# sensors.net
KiCad netlist of a schematic drawn in Altium Designer
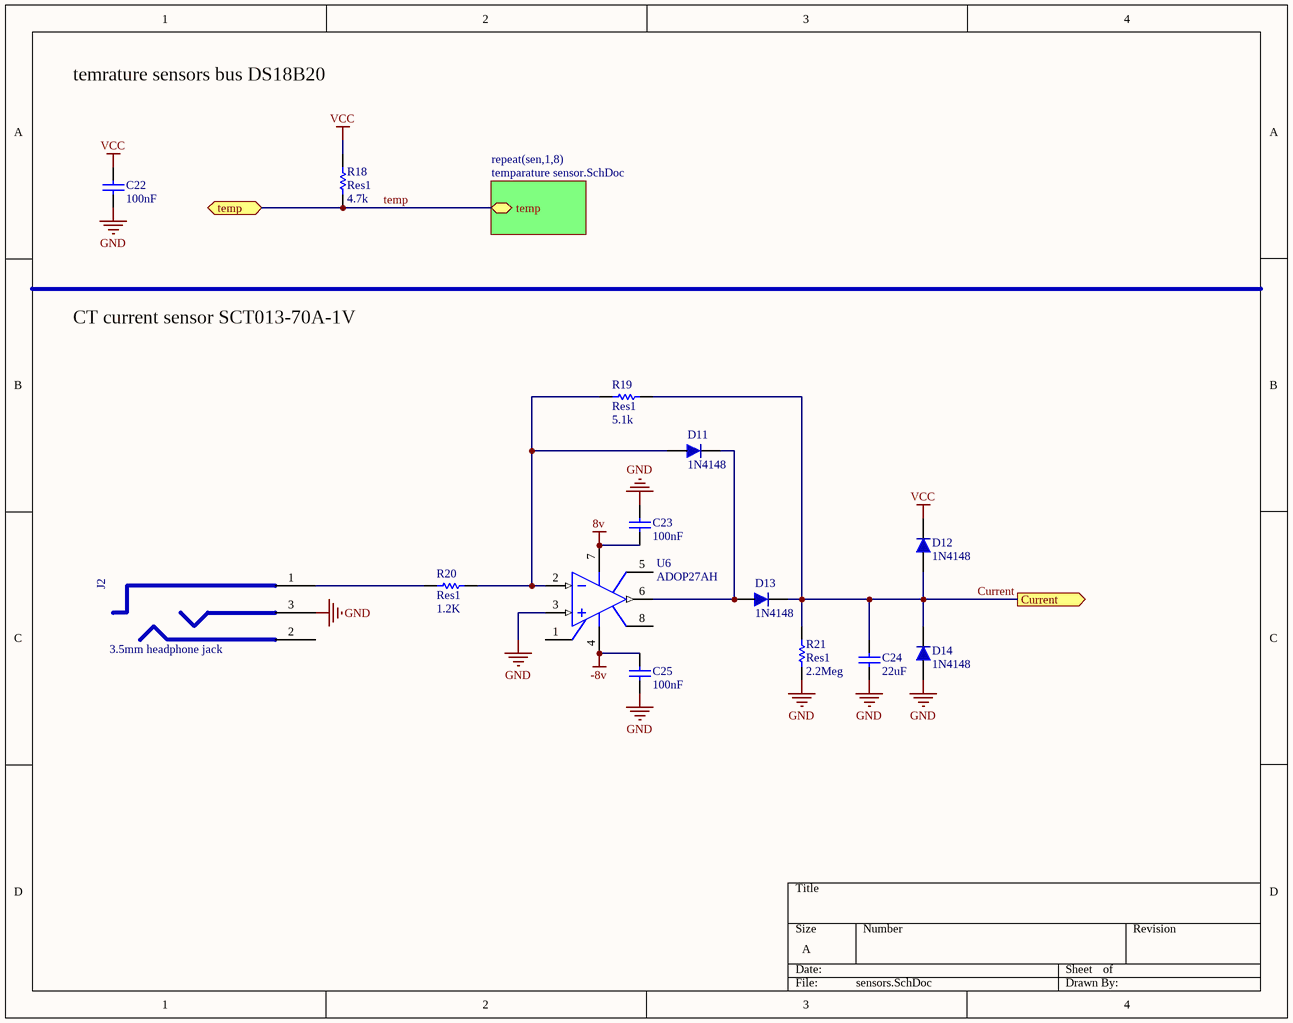
[diagram p0: sensors.SchDoc]

(export (version "E")
  (design (tool "Eeschema 10.0.6"))
  (components
    (comp (ref "C22")
      (value "100nF")
      (footprint "CAP 1206 (3216X15L)")
      (description "CAP-100Nf")
      (fields (field (name "Comment") "Cap"))
      (libsource (lib "Altium library (www.AVRelec.com)") (part "Cap ceramic"))
    )
    (comp (ref "C23")
      (value "100nF")
      (footprint "CAP 1206 (3216X15L)")
      (description "CAP-100Nf")
      (fields (field (name "Comment") "Cap"))
      (libsource (lib "Altium library (www.AVRelec.com)") (part "Cap ceramic"))
    )
    (comp (ref "C24")
      (value "22uF")
      (footprint "CAP 1206 (3216X15L)")
      (description "CAP-100Nf")
      (fields (field (name "Comment") "Cap"))
      (libsource (lib "Altium library (www.AVRelec.com)") (part "Cap ceramic"))
    )
    (comp (ref "C25")
      (value "100nF")
      (footprint "CAP 1206 (3216X15L)")
      (description "CAP-100Nf")
      (fields (field (name "Comment") "Cap"))
      (libsource (lib "Altium library (www.AVRelec.com)") (part "Cap ceramic"))
    )
    (comp (ref "D11")
      (value "1N4148")
      (footprint "LL4148")
      (description "DIODE GEN PURP 100V 200MA DO35")
      (fields (field (name "PUBLISHER") "Abbas Basereh"))
      (libsource (lib "Altium (2)") (part "1N4148"))
    )
    (comp (ref "D12")
      (value "1N4148")
      (footprint "LL4148")
      (description "DIODE GEN PURP 100V 200MA DO35")
      (fields (field (name "PUBLISHER") "Abbas Basereh"))
      (libsource (lib "Altium (2)") (part "1N4148"))
    )
    (comp (ref "D13")
      (value "1N4148")
      (footprint "LL4148")
      (description "DIODE GEN PURP 100V 200MA DO35")
      (fields (field (name "PUBLISHER") "Abbas Basereh"))
      (libsource (lib "Altium (2)") (part "1N4148"))
    )
    (comp (ref "D14")
      (value "1N4148")
      (footprint "LL4148")
      (description "DIODE GEN PURP 100V 200MA DO35")
      (fields (field (name "PUBLISHER") "Abbas Basereh"))
      (libsource (lib "Altium (2)") (part "1N4148"))
    )
    (comp (ref "J2")
      (value "3.5mm headphone jack")
      (footprint "phone jack")
      (libsource (lib "chiller") (part "phone jack"))
    )
    (comp (ref "R18")
      (value "Res1")
      (footprint "RES 1206 (3216X08L)")
      (description "Resistor")
      (fields (field (name "ALTIUM_VALUE") "4.7k") (field (name "PUBLISHER") "Altium Limited"))
      (libsource (lib "Miscellaneous Devices") (part "Res1"))
    )
    (comp (ref "R19")
      (value "Res1")
      (footprint "RES 1206 (3216X08L)")
      (description "Resistor")
      (fields (field (name "ALTIUM_VALUE") "5.1k") (field (name "PUBLISHER") "Altium Limited"))
      (libsource (lib "Miscellaneous Devices") (part "Res1"))
    )
    (comp (ref "R20")
      (value "Res1")
      (footprint "RES 1206 (3216X08L)")
      (description "Resistor")
      (fields (field (name "ALTIUM_VALUE") "1.2K") (field (name "PUBLISHER") "Altium Limited"))
      (libsource (lib "Miscellaneous Devices") (part "Res1"))
    )
    (comp (ref "R21")
      (value "Res1")
      (footprint "RES 1206 (3216X08L)")
      (description "Resistor")
      (fields (field (name "ALTIUM_VALUE") "2.2Meg") (field (name "PUBLISHER") "Altium Limited"))
      (libsource (lib "Miscellaneous Devices") (part "Res1"))
    )
    (comp (ref "U6")
      (value "ADOP27AH")
      (footprint "SOIC8-Narrow")
      (description "Ultra-Low Noise, Precision Operational Amplifier")
      (fields (field (name "PUBLISHER") "Altium Limited"))
      (libsource (lib "AD Operational Amplifier") (part "ADOP27AH"))
    )
  )
  (nets
    (net (code "1") (name "-8v") (class "Default")
      (node (ref "C25") (pin "2") (pinfunction "2_2") (pintype "passive"))
      (node (ref "U6") (pin "4") (pinfunction "V-_4") (pintype "power_in"))
    )
    (net (code "2") (name "/Current") (class "Default")
      (node (ref "C24") (pin "2") (pinfunction "2_2") (pintype "passive"))
      (node (ref "D12") (pin "1") (pintype "passive"))
      (node (ref "D13") (pin "2") (pintype "passive"))
      (node (ref "D14") (pin "2") (pintype "passive"))
      (node (ref "R19") (pin "2") (pinfunction "2_2") (pintype "passive"))
      (node (ref "R21") (pin "2") (pinfunction "2_2") (pintype "passive"))
    )
    (net (code "3") (name "/temp") (class "Default")
      (node (ref "R18") (pin "1") (pinfunction "1_1") (pintype "passive"))
    )
    (net (code "4") (name "8v") (class "Default")
      (node (ref "C23") (pin "1") (pinfunction "1_1") (pintype "passive"))
      (node (ref "U6") (pin "7") (pinfunction "V+_7") (pintype "power_in"))
    )
    (net (code "5") (name "GND") (class "Default")
      (node (ref "C22") (pin "1") (pinfunction "1_1") (pintype "passive"))
      (node (ref "C23") (pin "2") (pinfunction "2_2") (pintype "passive"))
      (node (ref "C24") (pin "1") (pinfunction "1_1") (pintype "passive"))
      (node (ref "C25") (pin "1") (pinfunction "1_1") (pintype "passive"))
      (node (ref "D14") (pin "1") (pintype "passive"))
      (node (ref "J2") (pin "3") (pinfunction "Tip_3") (pintype "passive"))
      (node (ref "R21") (pin "1") (pinfunction "1_1") (pintype "passive"))
      (node (ref "U6") (pin "3") (pinfunction "IN+_3") (pintype "input"))
    )
    (net (code "6") (name "Net-(J2-Ring-Pad1)") (class "Default")
      (node (ref "J2") (pin "1") (pinfunction "Ring_1") (pintype "passive"))
      (node (ref "R20") (pin "1") (pinfunction "1_1") (pintype "passive"))
    )
    (net (code "7") (name "Net-(U6-IN-)") (class "Default")
      (node (ref "D11") (pin "1") (pintype "passive"))
      (node (ref "R19") (pin "1") (pinfunction "1_1") (pintype "passive"))
      (node (ref "R20") (pin "2") (pinfunction "2_2") (pintype "passive"))
      (node (ref "U6") (pin "2") (pinfunction "IN-_2") (pintype "input"))
    )
    (net (code "8") (name "Net-(U6-OUT)") (class "Default")
      (node (ref "D11") (pin "2") (pintype "passive"))
      (node (ref "D13") (pin "1") (pintype "passive"))
      (node (ref "U6") (pin "6") (pinfunction "OUT_6") (pintype "output"))
    )
    (net (code "9") (name "VCC") (class "Default")
      (node (ref "C22") (pin "2") (pinfunction "2_2") (pintype "passive"))
      (node (ref "D12") (pin "2") (pintype "passive"))
      (node (ref "R18") (pin "2") (pinfunction "2_2") (pintype "passive"))
    )
    (net (code "10") (name "unconnected-(J2-Ring-Pad2)") (class "Default")
      (node (ref "J2") (pin "2") (pinfunction "Ring_2") (pintype "passive"))
    )
    (net (code "11") (name "unconnected-(U6-NC-Pad5)") (class "Default")
      (node (ref "U6") (pin "5") (pinfunction "NC_5") (pintype "passive"))
    )
    (net (code "12") (name "unconnected-(U6-OS_NULL-Pad1)") (class "Default")
      (node (ref "U6") (pin "1") (pinfunction "OS_NULL_1") (pintype "passive"))
    )
    (net (code "13") (name "unconnected-(U6-OS_NULL-Pad8)") (class "Default")
      (node (ref "U6") (pin "8") (pinfunction "OS_NULL_8") (pintype "passive"))
    )
  )
)
